# hviezda.net
KiCad netlist of a schematic drawn in EAGLE
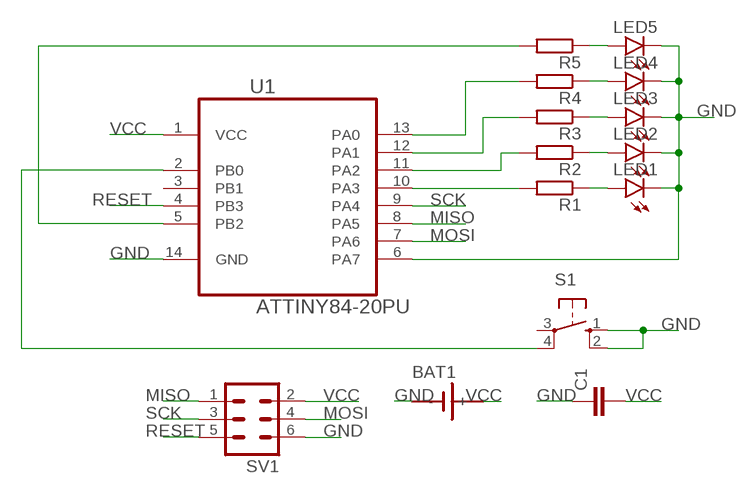
[diagram p0: schematic, sheet 1]

(export (version "E")
  (design (tool "Eeschema 10.0.6"))
  (components
    (comp (ref "BAT1")
      (value "SN2032")
      (footprint "eagle-import:SN2032")
      (libsource (lib "eagle-import") (part "SN2032"))
    )
    (comp (ref "C1")
      (value "C-EU050-024X044")
      (footprint "eagle-import:C050-024X044")
      (libsource (lib "eagle-import") (part "C-EU050-024X044"))
    )
    (comp (ref "LED1")
      (value "LED5MM")
      (footprint "eagle-import:LED5MM")
      (libsource (lib "eagle-import") (part "LED5MM"))
    )
    (comp (ref "LED2")
      (value "LED5MM")
      (footprint "eagle-import:LED5MM")
      (libsource (lib "eagle-import") (part "LED5MM"))
    )
    (comp (ref "LED3")
      (value "LED5MM")
      (footprint "eagle-import:LED5MM")
      (libsource (lib "eagle-import") (part "LED5MM"))
    )
    (comp (ref "LED4")
      (value "LED5MM")
      (footprint "eagle-import:LED5MM")
      (libsource (lib "eagle-import") (part "LED5MM"))
    )
    (comp (ref "LED5")
      (value "LED5MM")
      (footprint "eagle-import:LED5MM")
      (libsource (lib "eagle-import") (part "LED5MM"))
    )
    (comp (ref "R1")
      (value "R-EU_0207/10")
      (footprint "eagle-import:0207_10")
      (libsource (lib "eagle-import") (part "R-EU_0207/10"))
    )
    (comp (ref "R2")
      (value "R-EU_0207/10")
      (footprint "eagle-import:0207_10")
      (libsource (lib "eagle-import") (part "R-EU_0207/10"))
    )
    (comp (ref "R3")
      (value "R-EU_0207/10")
      (footprint "eagle-import:0207_10")
      (libsource (lib "eagle-import") (part "R-EU_0207/10"))
    )
    (comp (ref "R4")
      (value "R-EU_0207/10")
      (footprint "eagle-import:0207_10")
      (libsource (lib "eagle-import") (part "R-EU_0207/10"))
    )
    (comp (ref "R5")
      (value "R-EU_0207/10")
      (footprint "eagle-import:0207_10")
      (libsource (lib "eagle-import") (part "R-EU_0207/10"))
    )
    (comp (ref "S1")
      (value "10-XX")
      (footprint "eagle-import:B3F-10XX")
      (fields (field (name "MPN") "B3F-1000"))
      (libsource (lib "eagle-import") (part "10-XX"))
    )
    (comp (ref "SV1")
      (value "MA03-2")
      (footprint "eagle-import:MA03-2")
      (libsource (lib "eagle-import") (part "MA03-2"))
    )
    (comp (ref "U1")
      (value "ATTINY84-20PU")
      (footprint "eagle-import:DIP254P762X533-14")
      (libsource (lib "eagle-import") (part "ATTINY84-20PU"))
    )
  )
  (nets
    (net (code "1") (name "/GND") (class "Default")
      (node (ref "BAT1") (pin "-") (pinfunction "-_-") (pintype "passive"))
      (node (ref "C1") (pin "1") (pinfunction "1_1") (pintype "passive"))
      (node (ref "LED1") (pin "K") (pinfunction "C_K") (pintype "passive"))
      (node (ref "LED2") (pin "K") (pinfunction "C_K") (pintype "passive"))
      (node (ref "LED3") (pin "K") (pinfunction "C_K") (pintype "passive"))
      (node (ref "LED4") (pin "K") (pinfunction "C_K") (pintype "passive"))
      (node (ref "LED5") (pin "K") (pinfunction "C_K") (pintype "passive"))
      (node (ref "S1") (pin "1") (pinfunction "S_1") (pintype "passive"))
      (node (ref "S1") (pin "2") (pinfunction "S1_2") (pintype "passive"))
      (node (ref "SV1") (pin "6") (pinfunction "6_6") (pintype "passive"))
      (node (ref "U1") (pin "14") (pinfunction "GND_14") (pintype "passive"))
      (node (ref "U1") (pin "6") (pinfunction "PA7_6") (pintype "bidirectional"))
    )
    (net (code "2") (name "/MISO") (class "Default")
      (node (ref "SV1") (pin "1") (pinfunction "1_1") (pintype "passive"))
      (node (ref "U1") (pin "8") (pinfunction "PA5_8") (pintype "bidirectional"))
    )
    (net (code "3") (name "/MOSI") (class "Default")
      (node (ref "SV1") (pin "4") (pinfunction "4_4") (pintype "passive"))
      (node (ref "U1") (pin "7") (pinfunction "PA6_7") (pintype "bidirectional"))
    )
    (net (code "4") (name "/RESET") (class "Default")
      (node (ref "SV1") (pin "5") (pinfunction "5_5") (pintype "passive"))
      (node (ref "U1") (pin "4") (pinfunction "PB3_4") (pintype "bidirectional"))
    )
    (net (code "5") (name "/SCK") (class "Default")
      (node (ref "SV1") (pin "3") (pinfunction "3_3") (pintype "passive"))
      (node (ref "U1") (pin "9") (pinfunction "PA4_9") (pintype "bidirectional"))
    )
    (net (code "6") (name "/VCC") (class "Default")
      (node (ref "BAT1") (pin "+") (pinfunction "+_+") (pintype "passive"))
      (node (ref "C1") (pin "2") (pinfunction "2_2") (pintype "passive"))
      (node (ref "SV1") (pin "2") (pinfunction "2_2") (pintype "passive"))
      (node (ref "U1") (pin "1") (pinfunction "VCC_1") (pintype "power_in"))
    )
    (net (code "7") (name "Net-(LED1-PadA)") (class "Default")
      (node (ref "LED1") (pin "A") (pinfunction "A_A") (pintype "passive"))
      (node (ref "R1") (pin "1") (pinfunction "1_1") (pintype "passive"))
    )
    (net (code "8") (name "Net-(LED2-PadA)") (class "Default")
      (node (ref "LED2") (pin "A") (pinfunction "A_A") (pintype "passive"))
      (node (ref "R2") (pin "1") (pinfunction "1_1") (pintype "passive"))
    )
    (net (code "9") (name "Net-(LED3-PadA)") (class "Default")
      (node (ref "LED3") (pin "A") (pinfunction "A_A") (pintype "passive"))
      (node (ref "R3") (pin "1") (pinfunction "1_1") (pintype "passive"))
    )
    (net (code "10") (name "Net-(LED4-PadA)") (class "Default")
      (node (ref "LED4") (pin "A") (pinfunction "A_A") (pintype "passive"))
      (node (ref "R4") (pin "1") (pinfunction "1_1") (pintype "passive"))
    )
    (net (code "11") (name "Net-(LED5-PadA)") (class "Default")
      (node (ref "LED5") (pin "A") (pinfunction "A_A") (pintype "passive"))
      (node (ref "R5") (pin "1") (pinfunction "1_1") (pintype "passive"))
    )
    (net (code "12") (name "Net-(S1-P1)") (class "Default")
      (node (ref "S1") (pin "4") (pinfunction "P1_4") (pintype "passive"))
      (node (ref "U1") (pin "2") (pinfunction "PB0_2") (pintype "bidirectional"))
    )
    (net (code "13") (name "Net-(U1-PA0)") (class "Default")
      (node (ref "R4") (pin "2") (pinfunction "2_2") (pintype "passive"))
      (node (ref "U1") (pin "13") (pinfunction "PA0_13") (pintype "bidirectional"))
    )
    (net (code "14") (name "Net-(U1-PA1)") (class "Default")
      (node (ref "R3") (pin "2") (pinfunction "2_2") (pintype "passive"))
      (node (ref "U1") (pin "12") (pinfunction "PA1_12") (pintype "bidirectional"))
    )
    (net (code "15") (name "Net-(U1-PA2)") (class "Default")
      (node (ref "R2") (pin "2") (pinfunction "2_2") (pintype "passive"))
      (node (ref "U1") (pin "11") (pinfunction "PA2_11") (pintype "bidirectional"))
    )
    (net (code "16") (name "Net-(U1-PA3)") (class "Default")
      (node (ref "R1") (pin "2") (pinfunction "2_2") (pintype "passive"))
      (node (ref "U1") (pin "10") (pinfunction "PA3_10") (pintype "bidirectional"))
    )
    (net (code "17") (name "Net-(U1-PB2)") (class "Default")
      (node (ref "R5") (pin "2") (pinfunction "2_2") (pintype "passive"))
      (node (ref "U1") (pin "5") (pinfunction "PB2_5") (pintype "bidirectional"))
    )
    (net (code "18") (name "unconnected-(S1-P-Pad3)") (class "Default")
      (node (ref "S1") (pin "3") (pinfunction "P_3") (pintype "passive"))
    )
    (net (code "19") (name "unconnected-(U1-PB1-Pad3)") (class "Default")
      (node (ref "U1") (pin "3") (pinfunction "PB1_3") (pintype "bidirectional"))
    )
  )
)
